# Relay_shield.net
KiCad netlist of a schematic drawn in EAGLE
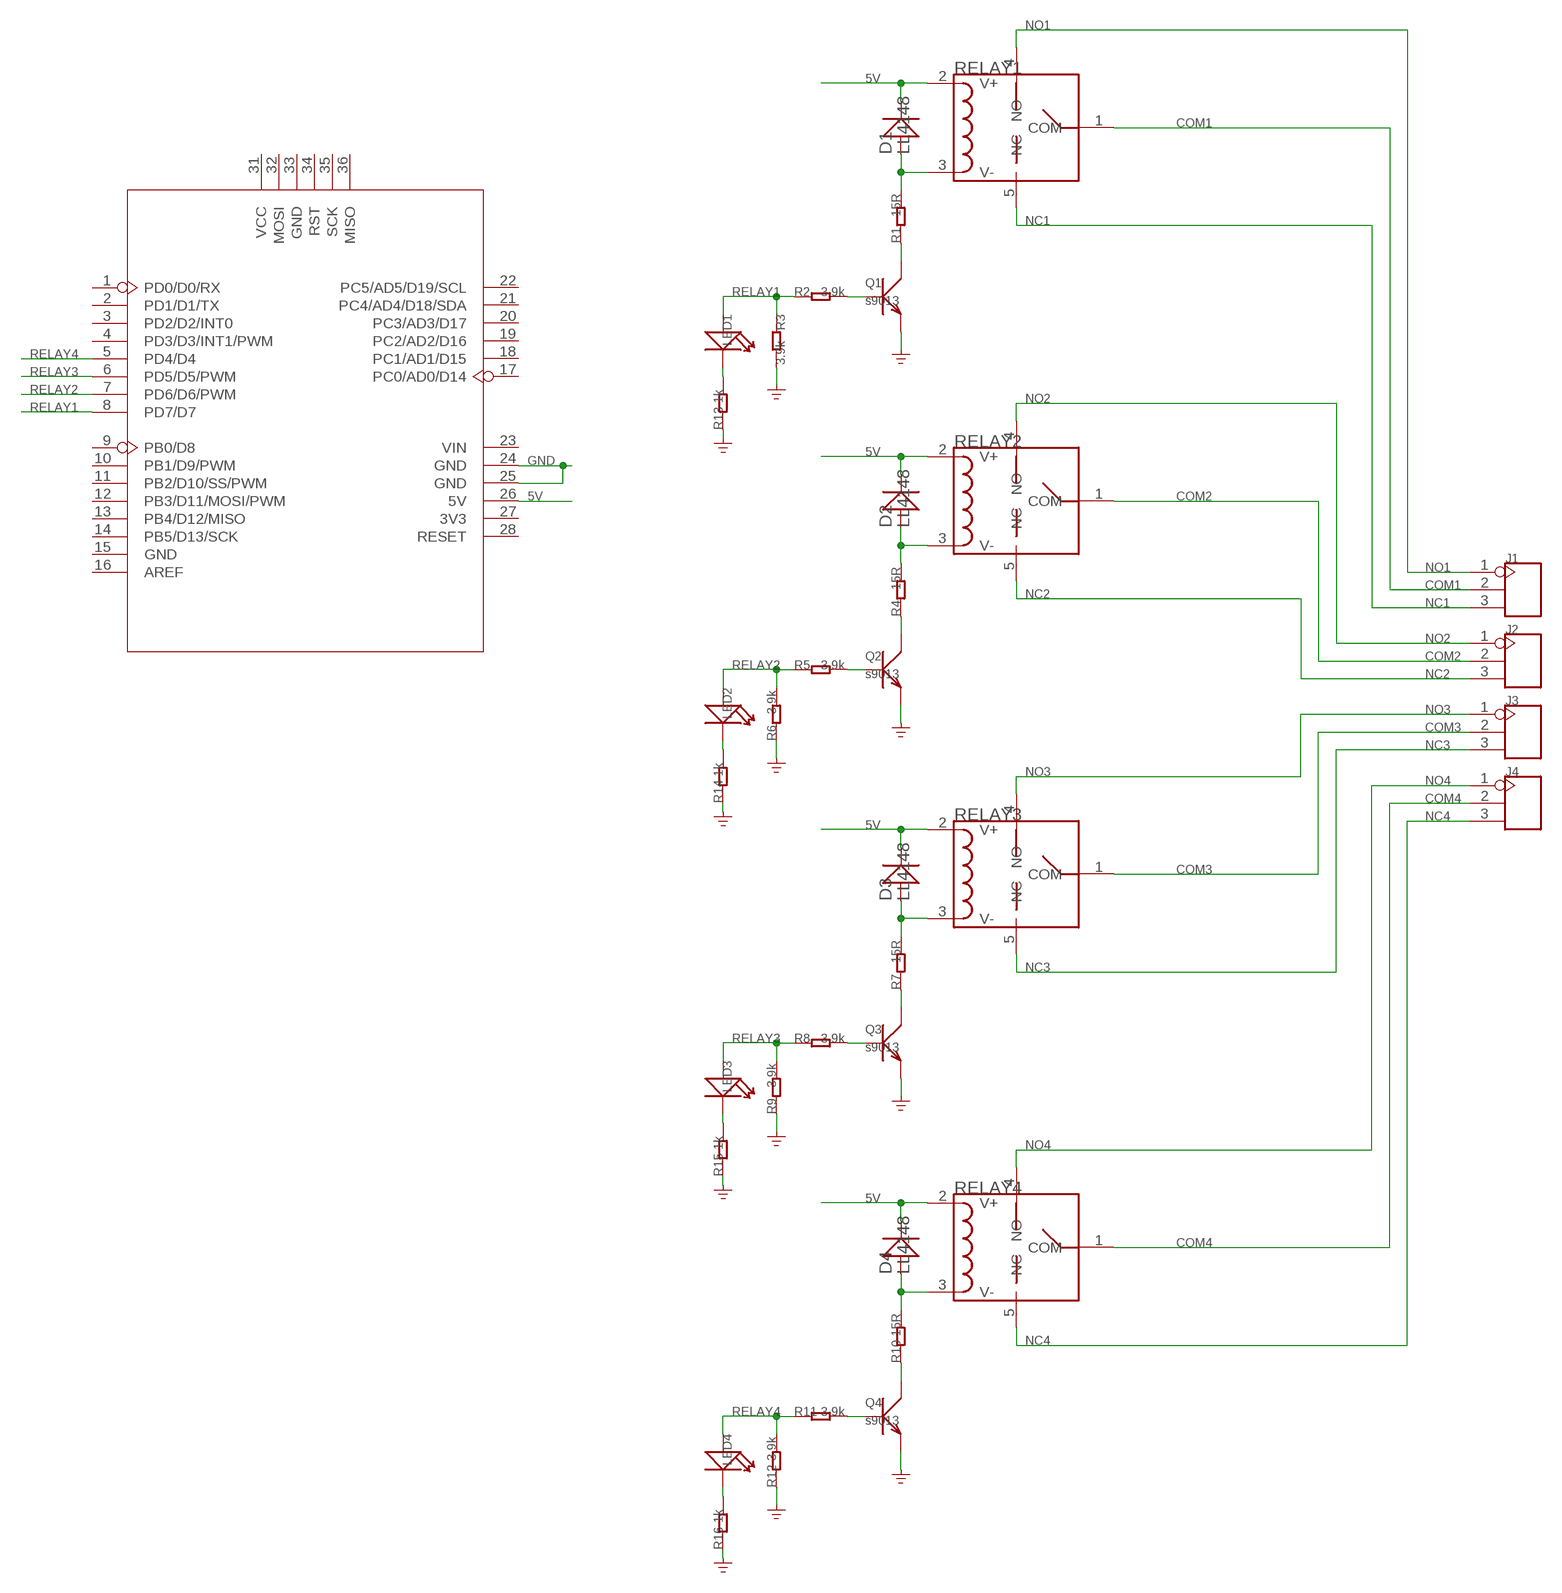
[diagram p0: schematic, sheet 1]

(export (version "E")
  (design (tool "Eeschema 10.0.6"))
  (components
    (comp (ref "D1")
      (value "LL4148")
      (footprint "eagle-import:D1206")
      (libsource (lib "eagle-import") (part "D-1206"))
    )
    (comp (ref "D2")
      (value "LL4148")
      (footprint "eagle-import:D1206")
      (libsource (lib "eagle-import") (part "D-1206"))
    )
    (comp (ref "D3")
      (value "LL4148")
      (footprint "eagle-import:D1206")
      (libsource (lib "eagle-import") (part "D-1206"))
    )
    (comp (ref "D4")
      (value "LL4148")
      (footprint "eagle-import:D1206")
      (libsource (lib "eagle-import") (part "D-1206"))
    )
    (comp (ref "J1")
      (value "SCREW-TERMINAL-3P'5.08'")
      (footprint "eagle-import:3P-5.08")
      (libsource (lib "eagle-import") (part "SCREW-TERMINAL-3P'5.08'"))
    )
    (comp (ref "J2")
      (value "SCREW-TERMINAL-3P'5.08'")
      (footprint "eagle-import:3P-5.08")
      (libsource (lib "eagle-import") (part "SCREW-TERMINAL-3P'5.08'"))
    )
    (comp (ref "J3")
      (value "SCREW-TERMINAL-3P'5.08'")
      (footprint "eagle-import:3P-5.08")
      (libsource (lib "eagle-import") (part "SCREW-TERMINAL-3P'5.08'"))
    )
    (comp (ref "J4")
      (value "SCREW-TERMINAL-3P'5.08'")
      (footprint "eagle-import:3P-5.08")
      (libsource (lib "eagle-import") (part "SCREW-TERMINAL-3P'5.08'"))
    )
    (comp (ref "LED1")
      (value "LED'0603'")
      (footprint "eagle-import:LED-0603")
      (libsource (lib "eagle-import") (part "LED'0603'"))
    )
    (comp (ref "LED2")
      (value "LED'0603'")
      (footprint "eagle-import:LED-0603")
      (libsource (lib "eagle-import") (part "LED'0603'"))
    )
    (comp (ref "LED3")
      (value "LED'0603'")
      (footprint "eagle-import:LED-0603")
      (libsource (lib "eagle-import") (part "LED'0603'"))
    )
    (comp (ref "LED4")
      (value "LED'0603'")
      (footprint "eagle-import:LED-0603")
      (libsource (lib "eagle-import") (part "LED'0603'"))
    )
    (comp (ref "Q1")
      (value "s9013")
      (footprint "eagle-import:SOT23")
      (libsource (lib "eagle-import") (part "TRANSISTOR-NPN-SOT23''"))
    )
    (comp (ref "Q2")
      (value "s9013")
      (footprint "eagle-import:SOT23")
      (libsource (lib "eagle-import") (part "TRANSISTOR-NPN-SOT23''"))
    )
    (comp (ref "Q3")
      (value "s9013")
      (footprint "eagle-import:SOT23")
      (libsource (lib "eagle-import") (part "TRANSISTOR-NPN-SOT23''"))
    )
    (comp (ref "Q4")
      (value "s9013")
      (footprint "eagle-import:SOT23")
      (libsource (lib "eagle-import") (part "TRANSISTOR-NPN-SOT23''"))
    )
    (comp (ref "R1")
      (value "15R")
      (footprint "eagle-import:R0603")
      (libsource (lib "eagle-import") (part "R-0603"))
    )
    (comp (ref "R2")
      (value "3.9k")
      (footprint "eagle-import:R0603")
      (libsource (lib "eagle-import") (part "R-0603"))
    )
    (comp (ref "R3")
      (value "3.9k")
      (footprint "eagle-import:R0603")
      (libsource (lib "eagle-import") (part "R-0603"))
    )
    (comp (ref "R4")
      (value "15R")
      (footprint "eagle-import:R0603")
      (libsource (lib "eagle-import") (part "R-0603"))
    )
    (comp (ref "R5")
      (value "3.9k")
      (footprint "eagle-import:R0603")
      (libsource (lib "eagle-import") (part "R-0603"))
    )
    (comp (ref "R6")
      (value "3.9k")
      (footprint "eagle-import:R0603")
      (libsource (lib "eagle-import") (part "R-0603"))
    )
    (comp (ref "R7")
      (value "15R")
      (footprint "eagle-import:R0603")
      (libsource (lib "eagle-import") (part "R-0603"))
    )
    (comp (ref "R8")
      (value "3.9k")
      (footprint "eagle-import:R0603")
      (libsource (lib "eagle-import") (part "R-0603"))
    )
    (comp (ref "R9")
      (value "3.9k")
      (footprint "eagle-import:R0603")
      (libsource (lib "eagle-import") (part "R-0603"))
    )
    (comp (ref "R10")
      (value "15R")
      (footprint "eagle-import:R0603")
      (libsource (lib "eagle-import") (part "R-0603"))
    )
    (comp (ref "R11")
      (value "3.9k")
      (footprint "eagle-import:R0603")
      (libsource (lib "eagle-import") (part "R-0603"))
    )
    (comp (ref "R12")
      (value "3.9k")
      (footprint "eagle-import:R0603")
      (libsource (lib "eagle-import") (part "R-0603"))
    )
    (comp (ref "R13")
      (value "1k")
      (footprint "eagle-import:R0603")
      (libsource (lib "eagle-import") (part "R-0603"))
    )
    (comp (ref "R14")
      (value "1k")
      (footprint "eagle-import:R0603")
      (libsource (lib "eagle-import") (part "R-0603"))
    )
    (comp (ref "R15")
      (value "1k")
      (footprint "eagle-import:R0603")
      (libsource (lib "eagle-import") (part "R-0603"))
    )
    (comp (ref "R16")
      (value "1k")
      (footprint "eagle-import:R0603")
      (libsource (lib "eagle-import") (part "R-0603"))
    )
    (comp (ref "RELAY1")
      (value "RELAY-HLS8L-DC5V-S-C")
      (footprint "eagle-import:5P-19.0X15.5X15.8H")
      (libsource (lib "eagle-import") (part "RELAY-HLS8L-DC5V-S-C"))
    )
    (comp (ref "RELAY2")
      (value "RELAY-HLS8L-DC5V-S-C")
      (footprint "eagle-import:5P-19.0X15.5X15.8H")
      (libsource (lib "eagle-import") (part "RELAY-HLS8L-DC5V-S-C"))
    )
    (comp (ref "RELAY3")
      (value "RELAY-HLS8L-DC5V-S-C")
      (footprint "eagle-import:5P-19.0X15.5X15.8H")
      (libsource (lib "eagle-import") (part "RELAY-HLS8L-DC5V-S-C"))
    )
    (comp (ref "RELAY4")
      (value "RELAY-HLS8L-DC5V-S-C")
      (footprint "eagle-import:5P-19.0X15.5X15.8H")
      (libsource (lib "eagle-import") (part "RELAY-HLS8L-DC5V-S-C"))
    )
    (comp (ref "U1")
      (value "ARDUINO'W/O-SILK'")
      (footprint "eagle-import:ARDUINO-W_O-SILK")
      (libsource (lib "eagle-import") (part "ARDUINO'W/O-SILK'"))
    )
  )
  (nets
    (net (code "1") (name "/5V") (class "Default")
      (node (ref "D1") (pin "-") (pinfunction "-_-") (pintype "passive"))
      (node (ref "D2") (pin "-") (pinfunction "-_-") (pintype "passive"))
      (node (ref "D3") (pin "-") (pinfunction "-_-") (pintype "passive"))
      (node (ref "D4") (pin "-") (pinfunction "-_-") (pintype "passive"))
      (node (ref "RELAY1") (pin "2") (pinfunction "V+_2") (pintype "bidirectional"))
      (node (ref "RELAY2") (pin "2") (pinfunction "V+_2") (pintype "bidirectional"))
      (node (ref "RELAY3") (pin "2") (pinfunction "V+_2") (pintype "bidirectional"))
      (node (ref "RELAY4") (pin "2") (pinfunction "V+_2") (pintype "bidirectional"))
      (node (ref "U1") (pin "26") (pinfunction "5V_26") (pintype "bidirectional"))
    )
    (net (code "2") (name "/COM1") (class "Default")
      (node (ref "J1") (pin "2") (pinfunction "P$2_2") (pintype "bidirectional"))
      (node (ref "RELAY1") (pin "1") (pinfunction "COM_1") (pintype "bidirectional"))
    )
    (net (code "3") (name "/COM2") (class "Default")
      (node (ref "J2") (pin "2") (pinfunction "P$2_2") (pintype "bidirectional"))
      (node (ref "RELAY2") (pin "1") (pinfunction "COM_1") (pintype "bidirectional"))
    )
    (net (code "4") (name "/COM3") (class "Default")
      (node (ref "J3") (pin "2") (pinfunction "P$2_2") (pintype "bidirectional"))
      (node (ref "RELAY3") (pin "1") (pinfunction "COM_1") (pintype "bidirectional"))
    )
    (net (code "5") (name "/COM4") (class "Default")
      (node (ref "J4") (pin "2") (pinfunction "P$2_2") (pintype "bidirectional"))
      (node (ref "RELAY4") (pin "1") (pinfunction "COM_1") (pintype "bidirectional"))
    )
    (net (code "6") (name "/NC1") (class "Default")
      (node (ref "J1") (pin "3") (pinfunction "P$3_3") (pintype "bidirectional"))
      (node (ref "RELAY1") (pin "5") (pinfunction "NC_5") (pintype "bidirectional"))
    )
    (net (code "7") (name "/NC2") (class "Default")
      (node (ref "J2") (pin "3") (pinfunction "P$3_3") (pintype "bidirectional"))
      (node (ref "RELAY2") (pin "5") (pinfunction "NC_5") (pintype "bidirectional"))
    )
    (net (code "8") (name "/NC3") (class "Default")
      (node (ref "J3") (pin "3") (pinfunction "P$3_3") (pintype "bidirectional"))
      (node (ref "RELAY3") (pin "5") (pinfunction "NC_5") (pintype "bidirectional"))
    )
    (net (code "9") (name "/NC4") (class "Default")
      (node (ref "J4") (pin "3") (pinfunction "P$3_3") (pintype "bidirectional"))
      (node (ref "RELAY4") (pin "5") (pinfunction "NC_5") (pintype "bidirectional"))
    )
    (net (code "10") (name "/NO1") (class "Default")
      (node (ref "J1") (pin "1") (pinfunction "P$1_1") (pintype "bidirectional"))
      (node (ref "RELAY1") (pin "4") (pinfunction "NO_4") (pintype "bidirectional"))
    )
    (net (code "11") (name "/NO2") (class "Default")
      (node (ref "J2") (pin "1") (pinfunction "P$1_1") (pintype "bidirectional"))
      (node (ref "RELAY2") (pin "4") (pinfunction "NO_4") (pintype "bidirectional"))
    )
    (net (code "12") (name "/NO3") (class "Default")
      (node (ref "J3") (pin "1") (pinfunction "P$1_1") (pintype "bidirectional"))
      (node (ref "RELAY3") (pin "4") (pinfunction "NO_4") (pintype "bidirectional"))
    )
    (net (code "13") (name "/NO4") (class "Default")
      (node (ref "J4") (pin "1") (pinfunction "P$1_1") (pintype "bidirectional"))
      (node (ref "RELAY4") (pin "4") (pinfunction "NO_4") (pintype "bidirectional"))
    )
    (net (code "14") (name "/RELAY1") (class "Default")
      (node (ref "LED1") (pin "+") (pinfunction "+_+") (pintype "passive"))
      (node (ref "R2") (pin "1") (pinfunction "1_1") (pintype "passive"))
      (node (ref "R3") (pin "1") (pinfunction "1_1") (pintype "passive"))
      (node (ref "U1") (pin "8") (pinfunction "PD7/D7_8") (pintype "bidirectional"))
    )
    (net (code "15") (name "/RELAY2") (class "Default")
      (node (ref "LED2") (pin "+") (pinfunction "+_+") (pintype "passive"))
      (node (ref "R5") (pin "1") (pinfunction "1_1") (pintype "passive"))
      (node (ref "R6") (pin "2") (pinfunction "2_2") (pintype "passive"))
      (node (ref "U1") (pin "7") (pinfunction "PD6/D6/PWM_7") (pintype "bidirectional"))
    )
    (net (code "16") (name "/RELAY3") (class "Default")
      (node (ref "LED3") (pin "+") (pinfunction "+_+") (pintype "passive"))
      (node (ref "R8") (pin "1") (pinfunction "1_1") (pintype "passive"))
      (node (ref "R9") (pin "2") (pinfunction "2_2") (pintype "passive"))
      (node (ref "U1") (pin "6") (pinfunction "PD5/D5/PWM_6") (pintype "bidirectional"))
    )
    (net (code "17") (name "/RELAY4") (class "Default")
      (node (ref "LED4") (pin "+") (pinfunction "+_+") (pintype "passive"))
      (node (ref "R11") (pin "1") (pinfunction "1_1") (pintype "passive"))
      (node (ref "R12") (pin "2") (pinfunction "2_2") (pintype "passive"))
      (node (ref "U1") (pin "5") (pinfunction "PD4/D4_5") (pintype "bidirectional"))
    )
    (net (code "18") (name "GND_POWER") (class "Default")
      (node (ref "Q1") (pin "2") (pinfunction "E_2") (pintype "passive"))
      (node (ref "Q2") (pin "2") (pinfunction "E_2") (pintype "passive"))
      (node (ref "Q3") (pin "2") (pinfunction "E_2") (pintype "passive"))
      (node (ref "Q4") (pin "2") (pinfunction "E_2") (pintype "passive"))
      (node (ref "R12") (pin "1") (pinfunction "1_1") (pintype "passive"))
      (node (ref "R13") (pin "1") (pinfunction "1_1") (pintype "passive"))
      (node (ref "R14") (pin "1") (pinfunction "1_1") (pintype "passive"))
      (node (ref "R15") (pin "1") (pinfunction "1_1") (pintype "passive"))
      (node (ref "R16") (pin "1") (pinfunction "1_1") (pintype "passive"))
      (node (ref "R3") (pin "2") (pinfunction "2_2") (pintype "passive"))
      (node (ref "R6") (pin "1") (pinfunction "1_1") (pintype "passive"))
      (node (ref "R9") (pin "1") (pinfunction "1_1") (pintype "passive"))
      (node (ref "U1") (pin "24") (pinfunction "GND_24") (pintype "bidirectional"))
      (node (ref "U1") (pin "25") (pinfunction "GND_25") (pintype "bidirectional"))
    )
    (net (code "19") (name "Net-(LED1-Pad-)") (class "Default")
      (node (ref "LED1") (pin "-") (pinfunction "-_-") (pintype "passive"))
      (node (ref "R13") (pin "2") (pinfunction "2_2") (pintype "passive"))
    )
    (net (code "20") (name "Net-(LED2-Pad-)") (class "Default")
      (node (ref "LED2") (pin "-") (pinfunction "-_-") (pintype "passive"))
      (node (ref "R14") (pin "2") (pinfunction "2_2") (pintype "passive"))
    )
    (net (code "21") (name "Net-(LED3-Pad-)") (class "Default")
      (node (ref "LED3") (pin "-") (pinfunction "-_-") (pintype "passive"))
      (node (ref "R15") (pin "2") (pinfunction "2_2") (pintype "passive"))
    )
    (net (code "22") (name "Net-(LED4-Pad-)") (class "Default")
      (node (ref "LED4") (pin "-") (pinfunction "-_-") (pintype "passive"))
      (node (ref "R16") (pin "2") (pinfunction "2_2") (pintype "passive"))
    )
    (net (code "23") (name "Net-(Q1-B)") (class "Default")
      (node (ref "Q1") (pin "1") (pinfunction "B_1") (pintype "passive"))
      (node (ref "R2") (pin "2") (pinfunction "2_2") (pintype "passive"))
    )
    (net (code "24") (name "Net-(Q1-C)") (class "Default")
      (node (ref "Q1") (pin "3") (pinfunction "C_3") (pintype "passive"))
      (node (ref "R1") (pin "1") (pinfunction "1_1") (pintype "passive"))
    )
    (net (code "25") (name "Net-(Q2-B)") (class "Default")
      (node (ref "Q2") (pin "1") (pinfunction "B_1") (pintype "passive"))
      (node (ref "R5") (pin "2") (pinfunction "2_2") (pintype "passive"))
    )
    (net (code "26") (name "Net-(Q2-C)") (class "Default")
      (node (ref "Q2") (pin "3") (pinfunction "C_3") (pintype "passive"))
      (node (ref "R4") (pin "1") (pinfunction "1_1") (pintype "passive"))
    )
    (net (code "27") (name "Net-(Q3-B)") (class "Default")
      (node (ref "Q3") (pin "1") (pinfunction "B_1") (pintype "passive"))
      (node (ref "R8") (pin "2") (pinfunction "2_2") (pintype "passive"))
    )
    (net (code "28") (name "Net-(Q3-C)") (class "Default")
      (node (ref "Q3") (pin "3") (pinfunction "C_3") (pintype "passive"))
      (node (ref "R7") (pin "1") (pinfunction "1_1") (pintype "passive"))
    )
    (net (code "29") (name "Net-(Q4-B)") (class "Default")
      (node (ref "Q4") (pin "1") (pinfunction "B_1") (pintype "passive"))
      (node (ref "R11") (pin "2") (pinfunction "2_2") (pintype "passive"))
    )
    (net (code "30") (name "Net-(Q4-C)") (class "Default")
      (node (ref "Q4") (pin "3") (pinfunction "C_3") (pintype "passive"))
      (node (ref "R10") (pin "1") (pinfunction "1_1") (pintype "passive"))
    )
    (net (code "31") (name "Net-(RELAY1-V-)") (class "Default")
      (node (ref "D1") (pin "+") (pinfunction "+_+") (pintype "passive"))
      (node (ref "R1") (pin "2") (pinfunction "2_2") (pintype "passive"))
      (node (ref "RELAY1") (pin "3") (pinfunction "V-_3") (pintype "bidirectional"))
    )
    (net (code "32") (name "Net-(RELAY2-V-)") (class "Default")
      (node (ref "D2") (pin "+") (pinfunction "+_+") (pintype "passive"))
      (node (ref "R4") (pin "2") (pinfunction "2_2") (pintype "passive"))
      (node (ref "RELAY2") (pin "3") (pinfunction "V-_3") (pintype "bidirectional"))
    )
    (net (code "33") (name "Net-(RELAY3-V-)") (class "Default")
      (node (ref "D3") (pin "+") (pinfunction "+_+") (pintype "passive"))
      (node (ref "R7") (pin "2") (pinfunction "2_2") (pintype "passive"))
      (node (ref "RELAY3") (pin "3") (pinfunction "V-_3") (pintype "bidirectional"))
    )
    (net (code "34") (name "Net-(RELAY4-V-)") (class "Default")
      (node (ref "D4") (pin "+") (pinfunction "+_+") (pintype "passive"))
      (node (ref "R10") (pin "2") (pinfunction "2_2") (pintype "passive"))
      (node (ref "RELAY4") (pin "3") (pinfunction "V-_3") (pintype "bidirectional"))
    )
    (net (code "35") (name "unconnected-(U1-3V3-Pad27)") (class "Default")
      (node (ref "U1") (pin "27") (pinfunction "3V3_27") (pintype "bidirectional"))
    )
    (net (code "36") (name "unconnected-(U1-AREF-Pad16)") (class "Default")
      (node (ref "U1") (pin "16") (pinfunction "AREF_16") (pintype "bidirectional"))
    )
    (net (code "37") (name "unconnected-(U1-GND-Pad15)") (class "Default")
      (node (ref "U1") (pin "15") (pinfunction "GND_15") (pintype "bidirectional"))
    )
    (net (code "38") (name "unconnected-(U1-GND-Pad33)") (class "Default")
      (node (ref "U1") (pin "33") (pinfunction "GND_33") (pintype "bidirectional"))
    )
    (net (code "39") (name "unconnected-(U1-MISO-Pad36)") (class "Default")
      (node (ref "U1") (pin "36") (pinfunction "MISO_36") (pintype "bidirectional"))
    )
    (net (code "40") (name "unconnected-(U1-MOSI-Pad32)") (class "Default")
      (node (ref "U1") (pin "32") (pinfunction "MOSI_32") (pintype "bidirectional"))
    )
    (net (code "41") (name "unconnected-(U1-PB0{slash}D8-Pad9)") (class "Default")
      (node (ref "U1") (pin "9") (pinfunction "PB0/D8_9") (pintype "bidirectional"))
    )
    (net (code "42") (name "unconnected-(U1-PB1{slash}D9{slash}PWM-Pad10)") (class "Default")
      (node (ref "U1") (pin "10") (pinfunction "PB1/D9/PWM_10") (pintype "bidirectional"))
    )
    (net (code "43") (name "unconnected-(U1-PB2{slash}D10{slash}SS{slash}PWM-Pad11)") (class "Default")
      (node (ref "U1") (pin "11") (pinfunction "PB2/D10/SS/PWM_11") (pintype "bidirectional"))
    )
    (net (code "44") (name "unconnected-(U1-PB3{slash}D11{slash}MOSI{slash}PWM-Pad12)") (class "Default")
      (node (ref "U1") (pin "12") (pinfunction "PB3/D11/MOSI/PWM_12") (pintype "bidirectional"))
    )
    (net (code "45") (name "unconnected-(U1-PB4{slash}D12{slash}MISO-Pad13)") (class "Default")
      (node (ref "U1") (pin "13") (pinfunction "PB4/D12/MISO_13") (pintype "bidirectional"))
    )
    (net (code "46") (name "unconnected-(U1-PB5{slash}D13{slash}SCK-Pad14)") (class "Default")
      (node (ref "U1") (pin "14") (pinfunction "PB5/D13/SCK_14") (pintype "bidirectional"))
    )
    (net (code "47") (name "unconnected-(U1-PC0{slash}AD0{slash}D14-Pad17)") (class "Default")
      (node (ref "U1") (pin "17") (pinfunction "PC0/AD0/D14_17") (pintype "bidirectional"))
    )
    (net (code "48") (name "unconnected-(U1-PC1{slash}AD1{slash}D15-Pad18)") (class "Default")
      (node (ref "U1") (pin "18") (pinfunction "PC1/AD1/D15_18") (pintype "bidirectional"))
    )
    (net (code "49") (name "unconnected-(U1-PC2{slash}AD2{slash}D16-Pad19)") (class "Default")
      (node (ref "U1") (pin "19") (pinfunction "PC2/AD2/D16_19") (pintype "bidirectional"))
    )
    (net (code "50") (name "unconnected-(U1-PC3{slash}AD3{slash}D17-Pad20)") (class "Default")
      (node (ref "U1") (pin "20") (pinfunction "PC3/AD3/D17_20") (pintype "bidirectional"))
    )
    (net (code "51") (name "unconnected-(U1-PC4{slash}AD4{slash}D18{slash}SDA-Pad21)") (class "Default")
      (node (ref "U1") (pin "21") (pinfunction "PC4/AD4/D18/SDA_21") (pintype "bidirectional"))
    )
    (net (code "52") (name "unconnected-(U1-PC5{slash}AD5{slash}D19{slash}SCL-Pad22)") (class "Default")
      (node (ref "U1") (pin "22") (pinfunction "PC5/AD5/D19/SCL_22") (pintype "bidirectional"))
    )
    (net (code "53") (name "unconnected-(U1-PD0{slash}D0{slash}RX-Pad1)") (class "Default")
      (node (ref "U1") (pin "1") (pinfunction "PD0/D0/RX_1") (pintype "bidirectional"))
    )
    (net (code "54") (name "unconnected-(U1-PD1{slash}D1{slash}TX-Pad2)") (class "Default")
      (node (ref "U1") (pin "2") (pinfunction "PD1/D1/TX_2") (pintype "bidirectional"))
    )
    (net (code "55") (name "unconnected-(U1-PD2{slash}D2{slash}INT0-Pad3)") (class "Default")
      (node (ref "U1") (pin "3") (pinfunction "PD2/D2/INT0_3") (pintype "bidirectional"))
    )
    (net (code "56") (name "unconnected-(U1-PD3{slash}D3{slash}INT1{slash}PWM-Pad4)") (class "Default")
      (node (ref "U1") (pin "4") (pinfunction "PD3/D3/INT1/PWM_4") (pintype "bidirectional"))
    )
    (net (code "57") (name "unconnected-(U1-RESET-Pad28)") (class "Default")
      (node (ref "U1") (pin "28") (pinfunction "RESET_28") (pintype "bidirectional"))
    )
    (net (code "58") (name "unconnected-(U1-RST-Pad34)") (class "Default")
      (node (ref "U1") (pin "34") (pinfunction "RST_34") (pintype "bidirectional"))
    )
    (net (code "59") (name "unconnected-(U1-SCK-Pad35)") (class "Default")
      (node (ref "U1") (pin "35") (pinfunction "SCK_35") (pintype "bidirectional"))
    )
    (net (code "60") (name "unconnected-(U1-VCC-Pad31)") (class "Default")
      (node (ref "U1") (pin "31") (pinfunction "VCC_31") (pintype "bidirectional"))
    )
    (net (code "61") (name "unconnected-(U1-VIN-Pad23)") (class "Default")
      (node (ref "U1") (pin "23") (pinfunction "VIN_23") (pintype "bidirectional"))
    )
  )
)
